# fuente_dual_power.net
KiCad netlist of a schematic drawn in EAGLE
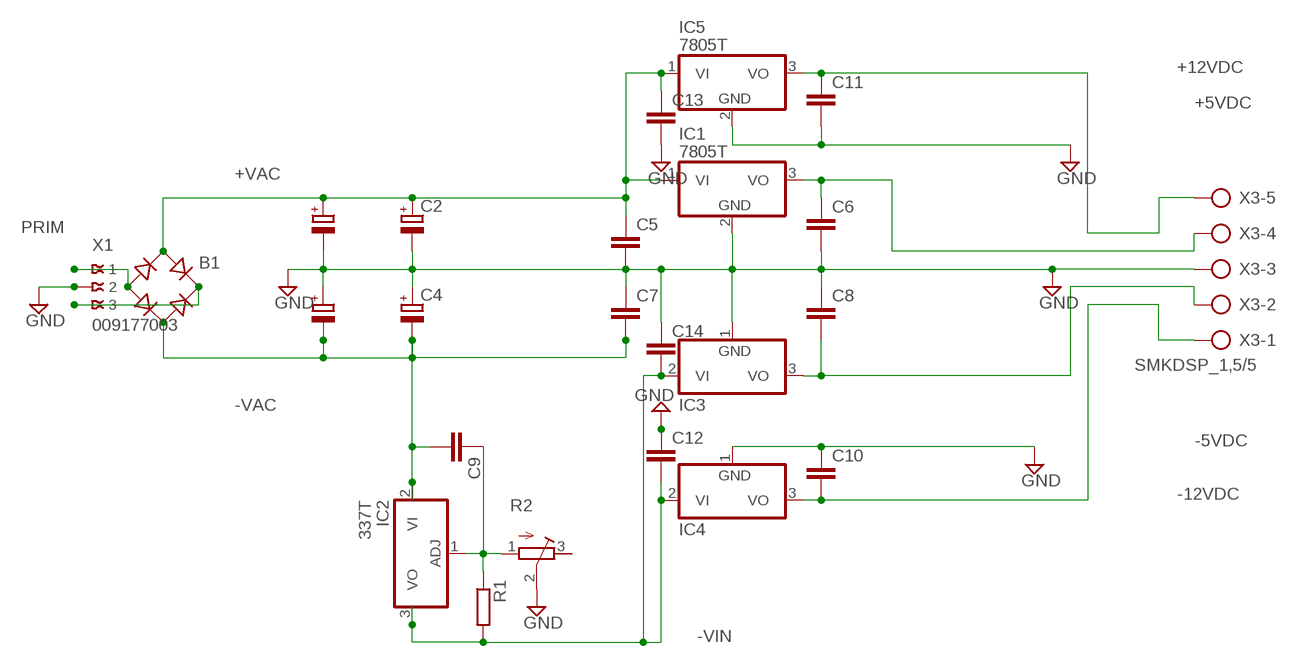
[diagram p0: schematic, sheet 1]

(export (version "E")
  (design (tool "Eeschema 10.0.6"))
  (components
    (comp (ref "B1")
      (value "RB1A")
      (footprint "eagle-import:RB1A")
      (libsource (lib "eagle-import") (part "RB1A"))
    )
    (comp (ref "C2")
      (value "CPOL-EUE1.8-4")
      (footprint "eagle-import:E1,8-4")
      (libsource (lib "eagle-import") (part "CPOL-EUE1.8-4"))
    )
    (comp (ref "C4")
      (value "CPOL-EUE1.8-4")
      (footprint "eagle-import:E1,8-4")
      (libsource (lib "eagle-import") (part "CPOL-EUE1.8-4"))
    )
    (comp (ref "C5")
      (value "C5/7.2")
      (footprint "eagle-import:C5B7.2")
      (libsource (lib "eagle-import") (part "C5/7.2"))
    )
    (comp (ref "C6")
      (value "C5/7.2")
      (footprint "eagle-import:C5B7.2")
      (libsource (lib "eagle-import") (part "C5/7.2"))
    )
    (comp (ref "C7")
      (value "C5/7.2")
      (footprint "eagle-import:C5B7.2")
      (libsource (lib "eagle-import") (part "C5/7.2"))
    )
    (comp (ref "C8")
      (value "C5/7.2")
      (footprint "eagle-import:C5B7.2")
      (fields (field (name "SPICEPREFIX") "C"))
      (libsource (lib "eagle-import") (part "C5/7.2"))
    )
    (comp (ref "C9")
      (value "C5/7.2")
      (footprint "eagle-import:C5B7.2")
      (libsource (lib "eagle-import") (part "C5/7.2"))
    )
    (comp (ref "C10")
      (value "C5/7.2")
      (footprint "eagle-import:C5B7.2")
      (fields (field (name "SPICEPREFIX") "C"))
      (libsource (lib "eagle-import") (part "C5/7.2"))
    )
    (comp (ref "C11")
      (value "C5/7.2")
      (footprint "eagle-import:C5B7.2")
      (fields (field (name "SPICEPREFIX") "C"))
      (libsource (lib "eagle-import") (part "C5/7.2"))
    )
    (comp (ref "C12")
      (value "C5/7.2")
      (footprint "eagle-import:C5B7.2")
      (libsource (lib "eagle-import") (part "C5/7.2"))
    )
    (comp (ref "C13")
      (value "C5/7.2")
      (footprint "eagle-import:C5B7.2")
      (libsource (lib "eagle-import") (part "C5/7.2"))
    )
    (comp (ref "C14")
      (value "C5/7.2")
      (footprint "eagle-import:C5B7.2")
      (libsource (lib "eagle-import") (part "C5/7.2"))
    )
    (comp (ref "IC1")
      (value "7805T")
      (footprint "eagle-import:TO220H")
      (libsource (lib "eagle-import") (part "78T05"))
    )
    (comp (ref "IC2")
      (value "337T")
      (footprint "eagle-import:TO220H")
      (libsource (lib "eagle-import") (part "337T"))
    )
    (comp (ref "IC3")
      (value "7905T")
      (footprint "eagle-import:TO220H")
      (libsource (lib "eagle-import") (part "79T05"))
    )
    (comp (ref "IC4")
      (value "7905T")
      (footprint "eagle-import:TO220H")
      (libsource (lib "eagle-import") (part "79T05"))
    )
    (comp (ref "IC5")
      (value "7805T")
      (footprint "eagle-import:TO220H")
      (libsource (lib "eagle-import") (part "78T05"))
    )
    (comp (ref "R1")
      (value "R-EU_0204/5")
      (footprint "eagle-import:0204_5")
      (libsource (lib "eagle-import") (part "R-EU_0204/5"))
    )
    (comp (ref "R2")
      (value "R-TRIMM64W")
      (footprint "eagle-import:RTRIM64W")
      (libsource (lib "eagle-import") (part "R-TRIMM64W"))
    )
    (comp (ref "X1")
      (value "009177003")
      (footprint "eagle-import:009177003")
      (fields (field (name "MPN") "009177003001006"))
      (libsource (lib "eagle-import") (part "00917?0037"))
    )
    (comp (ref "X3")
      (value "SMKDSP_1,5/5")
      (footprint "eagle-import:SMKDSP_1,5_5")
      (libsource (lib "eagle-import") (part "SMKDSP_1,5/5"))
    )
  )
  (nets
    (net (code "1") (name "/+5VDC") (class "Default")
      (node (ref "C6") (pin "1") (pinfunction "1_1") (pintype "passive"))
      (node (ref "IC1") (pin "3") (pinfunction "VO_3") (pintype "passive"))
      (node (ref "X3") (pin "4") (pinfunction "KL_4") (pintype "passive"))
    )
    (net (code "2") (name "/+12VDC") (class "Default")
      (node (ref "C11") (pin "1") (pinfunction "1_1") (pintype "passive"))
      (node (ref "IC5") (pin "3") (pinfunction "VO_3") (pintype "passive"))
      (node (ref "X3") (pin "5") (pinfunction "KL_5") (pintype "passive"))
    )
    (net (code "3") (name "/+VAC") (class "Default")
      (node (ref "B1") (pin "AC1") (pinfunction "AC1_AC1") (pintype "passive"))
      (node (ref "C13") (pin "1") (pinfunction "1_1") (pintype "passive"))
      (node (ref "C2") (pin "+") (pinfunction "+_+") (pintype "passive"))
      (node (ref "C5") (pin "1") (pinfunction "1_1") (pintype "passive"))
      (node (ref "IC1") (pin "1") (pinfunction "VI_1") (pintype "input"))
      (node (ref "IC5") (pin "1") (pinfunction "VI_1") (pintype "input"))
    )
    (net (code "4") (name "/-5VDC") (class "Default")
      (node (ref "C8") (pin "2") (pinfunction "2_2") (pintype "passive"))
      (node (ref "IC3") (pin "3") (pinfunction "VO_3") (pintype "passive"))
      (node (ref "X3") (pin "2") (pinfunction "KL_2") (pintype "passive"))
    )
    (net (code "5") (name "/-12VDC") (class "Default")
      (node (ref "C10") (pin "2") (pinfunction "2_2") (pintype "passive"))
      (node (ref "IC4") (pin "3") (pinfunction "VO_3") (pintype "passive"))
      (node (ref "X3") (pin "1") (pinfunction "KL_1") (pintype "passive"))
    )
    (net (code "6") (name "/-VAC") (class "Default")
      (node (ref "B1") (pin "AC2") (pinfunction "AC2_AC2") (pintype "passive"))
      (node (ref "C4") (pin "-") (pinfunction "-_-") (pintype "passive"))
      (node (ref "C7") (pin "2") (pinfunction "2_2") (pintype "passive"))
      (node (ref "C9") (pin "2") (pinfunction "2_2") (pintype "passive"))
      (node (ref "IC2") (pin "2") (pinfunction "VI_2") (pintype "input"))
    )
    (net (code "7") (name "/-VIN") (class "Default")
      (node (ref "C12") (pin "2") (pinfunction "2_2") (pintype "passive"))
      (node (ref "C14") (pin "2") (pinfunction "2_2") (pintype "passive"))
      (node (ref "IC2") (pin "3") (pinfunction "VO_3") (pintype "passive"))
      (node (ref "IC3") (pin "2") (pinfunction "VI_2") (pintype "input"))
      (node (ref "IC4") (pin "2") (pinfunction "VI_2") (pintype "input"))
      (node (ref "R1") (pin "2") (pinfunction "2_2") (pintype "passive"))
    )
    (net (code "8") (name "/PRIM") (class "Default")
      (node (ref "B1") (pin "-") (pinfunction "-_-") (pintype "passive"))
      (node (ref "X1") (pin "1") (pinfunction "1_1") (pintype "passive"))
    )
    (net (code "9") (name "GND") (class "Default")
      (node (ref "C10") (pin "1") (pinfunction "1_1") (pintype "passive"))
      (node (ref "C11") (pin "2") (pinfunction "2_2") (pintype "passive"))
      (node (ref "C12") (pin "1") (pinfunction "1_1") (pintype "passive"))
      (node (ref "C13") (pin "2") (pinfunction "2_2") (pintype "passive"))
      (node (ref "C14") (pin "1") (pinfunction "1_1") (pintype "passive"))
      (node (ref "C2") (pin "-") (pinfunction "-_-") (pintype "passive"))
      (node (ref "C4") (pin "+") (pinfunction "+_+") (pintype "passive"))
      (node (ref "C5") (pin "2") (pinfunction "2_2") (pintype "passive"))
      (node (ref "C6") (pin "2") (pinfunction "2_2") (pintype "passive"))
      (node (ref "C7") (pin "1") (pinfunction "1_1") (pintype "passive"))
      (node (ref "C8") (pin "1") (pinfunction "1_1") (pintype "passive"))
      (node (ref "IC1") (pin "2") (pinfunction "GND_2") (pintype "passive"))
      (node (ref "IC3") (pin "1") (pinfunction "GND_1") (pintype "passive"))
      (node (ref "IC4") (pin "1") (pinfunction "GND_1") (pintype "passive"))
      (node (ref "IC5") (pin "2") (pinfunction "GND_2") (pintype "passive"))
      (node (ref "R2") (pin "2") (pinfunction "S_2") (pintype "passive"))
      (node (ref "X1") (pin "2") (pinfunction "2_2") (pintype "passive"))
      (node (ref "X3") (pin "3") (pinfunction "KL_3") (pintype "passive"))
    )
    (net (code "10") (name "Net-(B1-Pad+)") (class "Default")
      (node (ref "B1") (pin "+") (pinfunction "+_+") (pintype "passive"))
      (node (ref "X1") (pin "3") (pinfunction "3_3") (pintype "passive"))
    )
    (net (code "11") (name "Net-(IC2-ADJ)") (class "Default")
      (node (ref "C9") (pin "1") (pinfunction "1_1") (pintype "passive"))
      (node (ref "IC2") (pin "1") (pinfunction "ADJ_1") (pintype "input"))
      (node (ref "R1") (pin "1") (pinfunction "1_1") (pintype "passive"))
      (node (ref "R2") (pin "1") (pinfunction "A_1") (pintype "passive"))
    )
    (net (code "12") (name "unconnected-(R2-E-Pad3)") (class "Default")
      (node (ref "R2") (pin "3") (pinfunction "E_3") (pintype "passive"))
    )
  )
)
